# 3V3_DIST_ZYNQ.net
KiCad netlist of a schematic drawn in Altium Designer
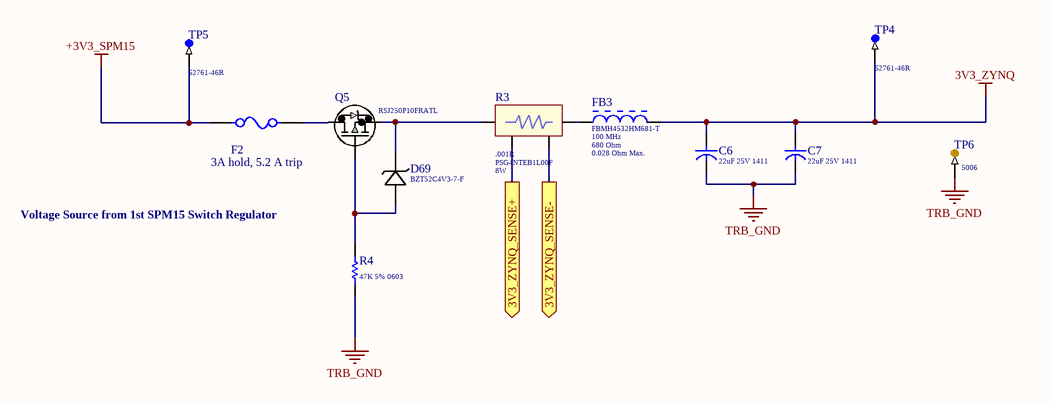
[diagram p0: 3V3_DIST_ZYNQ.SchDoc]

(export (version "E")
  (design (tool "Eeschema 10.0.6"))
  (components
    (comp (ref "C6")
      (value "Cap_Kemet_T521B226M025ATE100_22uF")
      (footprint "Cap_Kemet_T521B226M025ATE100_22uF")
      (description "Tantalum Capacitors - Polymer SMD 25V 22uF 1311 20% ESR=100mOhms")
      (fields (field (name "CAPACITANCE") "22uF 25V 1411"))
      (libsource (lib "Cap_Kemet_T521B226M025ATE100_22uF") (part "Cap_Kemet_T521B226M025ATE100_22uF"))
    )
    (comp (ref "C7")
      (value "Cap_Kemet_T521B226M025ATE100_22uF")
      (footprint "Cap_Kemet_T521B226M025ATE100_22uF")
      (description "Tantalum Capacitors - Polymer SMD 25V 22uF 1311 20% ESR=100mOhms")
      (fields (field (name "CAPACITANCE") "22uF 25V 1411"))
      (libsource (lib "Cap_Kemet_T521B226M025ATE100_22uF") (part "Cap_Kemet_T521B226M025ATE100_22uF"))
    )
    (comp (ref "D69")
      (value "BZT52C4V3-7-F")
      (footprint "SOD123")
      (description "Zener Diodes 500mW 4.3V Zener AEC-Q101 Qualified")
      (fields (field (name "SERIES") "BZT52C4V3-7-F"))
      (libsource (lib "4v3_zener_BZT52C4V3-7-F") (part "BZT52C4V3-7-F"))
    )
    (comp (ref "F2")
      (value "3A hold, 5.2 A trip")
      (footprint "Bel_0ZCF_MFG")
      (description "Resettable Fuses - PPTC 3A 24V PPTC 2920 SMD")
      (libsource (lib "Fuse_Bel_0ZCF0300BF2C_3A_hold") (part "0ZCF0300BF2C"))
    )
    (comp (ref "FB3")
      (value "FBMH4532HM681-T")
      (footprint "TAYO-FBMH4532-2_V")
      (fields
        (field (name "PARTNUMBER") "FBMH4532HM681-T")
        (field (name "MANUFACTURER") "Taiyo Yuden")
        (field (name "MEASURING FREQUENCY") "100 MHz")
        (field (name "NOMINAL IMPEDANCE") "680 Ohm")
        (field (name "DC RESISTANCE") "0.028 Ohm Max.")
      )
      (libsource (lib "Taiyo_Yuden_FBMH4532HM681") (part "FBMH4532HM681-T"))
    )
    (comp (ref "Q5")
      (value "Mos_ROHM_RSJ250P10FRATL_25A")
      (footprint "Mos_ROHM_RSJ250P10FRATL_25A")
      (description "MOSFET Pch -100V Vds -25A 0.05Rds(on) 60Qg")
      (fields (field (name "SERIES") "RSJ250P10FRATL"))
      (libsource (lib "Mos_ROHM_RSJ250P10FRATL_25A") (part "Mos_ROHM_RSJ250P10FRATL_25A"))
    )
    (comp (ref "R3")
      (value "SRes_KOA_PSG4NTEB1L00F_1mOhm")
      (footprint "SRes_KOA_PSG4NTEB1L00F_1mOhm")
      (description "Current Sense Resistors - SMD 1mOhm 8W 1% 50ppm AEC-Q200 Power Shunt")
      (fields
        (field (name "RESISTANCE") ".001R")
        (field (name "SERIES") "PSG4NTEB1L00F")
        (field (name "PARAMETER 1") "8W")
      )
      (libsource (lib "SRes_KOA_PSG4NTEB1L00F_1mOhm") (part "SRes_KOA_PSG4NTEB1L00F_1mOhm"))
    )
    (comp (ref "R4")
      (value "47K 5% 0603")
      (footprint "RESC0603(1608)_L")
      (description "47K 0.1W 5% 0603 (1608 Metric)  SMD")
      (fields (field (name "TOLERANCE") "5 %") (field (name "POWER") "0.1 W"))
      (libsource (lib "Altium Content Vault") (part "RES"))
    )
    (comp (ref "TP4")
      (value "TP_Harwin_S2761_46R")
      (footprint "TP_Harwin_S2761_46R")
      (description "Circuit Board Hardware - PCB SMT Mini Test Terminal, Reel")
      (fields (field (name "SERIES") "S2761-46R"))
      (libsource (lib "TP_Harwin_S2761_46R") (part "TP_Harwin_S2761_46R"))
    )
    (comp (ref "TP5")
      (value "TP_Harwin_S2761_46R")
      (footprint "TP_Harwin_S2761_46R")
      (description "Circuit Board Hardware - PCB SMT Mini Test Terminal, Reel")
      (fields (field (name "SERIES") "S2761-46R"))
      (libsource (lib "TP_Harwin_S2761_46R") (part "TP_Harwin_S2761_46R"))
    )
    (comp (ref "TP6")
      (value "TP_Keystone_Electronics_5006")
      (footprint "TP_Keystone_Electronics_5006")
      (description "Circuit Board Hardware - PCB TEST POINT BLK .063")
      (fields (field (name "SERIES") "5006"))
      (libsource (lib "TP_Keystone_Electronics_5006") (part "TP_Keystone_Electronics_5006"))
    )
  )
  (nets
    (net (code "1") (name "+3V3_SPM15") (class "Default")
      (node (ref "F2") (pin "1") (pinfunction "1_1") (pintype "passive"))
      (node (ref "TP5") (pin "1") (pinfunction "1_1") (pintype "input"))
    )
    (net (code "2") (name "/3V3_ZYNQ_SENSE+") (class "Default")
      (node (ref "R3") (pin "4") (pinfunction "4_4") (pintype "passive"))
    )
    (net (code "3") (name "/3V3_ZYNQ_SENSE-") (class "Default")
      (node (ref "R3") (pin "3") (pinfunction "3_3") (pintype "passive"))
    )
    (net (code "4") (name "3V3_ZYNQ") (class "Default")
      (node (ref "C6") (pin "1") (pinfunction "1_1") (pintype "passive"))
      (node (ref "C7") (pin "1") (pinfunction "1_1") (pintype "passive"))
      (node (ref "FB3") (pin "2") (pinfunction "2_2") (pintype "passive"))
      (node (ref "TP4") (pin "1") (pinfunction "1_1") (pintype "input"))
    )
    (net (code "5") (name "Net-(FB3-Pad1)") (class "Default")
      (node (ref "FB3") (pin "1") (pinfunction "1_1") (pintype "passive"))
      (node (ref "R3") (pin "2") (pinfunction "2_2") (pintype "passive"))
    )
    (net (code "6") (name "Net-(Q5-D)") (class "Default")
      (node (ref "F2") (pin "2") (pinfunction "2_2") (pintype "passive"))
      (node (ref "Q5") (pin "2") (pinfunction "D_2") (pintype "passive"))
    )
    (net (code "7") (name "Net-(Q5-G)") (class "Default")
      (node (ref "D69") (pin "2") (pinfunction "2_2") (pintype "passive"))
      (node (ref "Q5") (pin "1") (pinfunction "G_1") (pintype "passive"))
      (node (ref "R4") (pin "2") (pinfunction "2_2") (pintype "passive"))
    )
    (net (code "8") (name "Net-(Q5-S)") (class "Default")
      (node (ref "D69") (pin "1") (pinfunction "1_1") (pintype "passive"))
      (node (ref "Q5") (pin "3") (pinfunction "S_3") (pintype "passive"))
      (node (ref "R3") (pin "1") (pinfunction "1_1") (pintype "passive"))
    )
    (net (code "9") (name "TRB_GND") (class "Default")
      (node (ref "C6") (pin "2") (pinfunction "2_2") (pintype "passive"))
      (node (ref "C7") (pin "2") (pinfunction "2_2") (pintype "passive"))
      (node (ref "R4") (pin "1") (pinfunction "1_1") (pintype "passive"))
      (node (ref "TP6") (pin "1") (pinfunction "1_1") (pintype "input"))
    )
  )
)
